# boxer_pH.net
KiCad netlist of a schematic drawn in Altium Designer
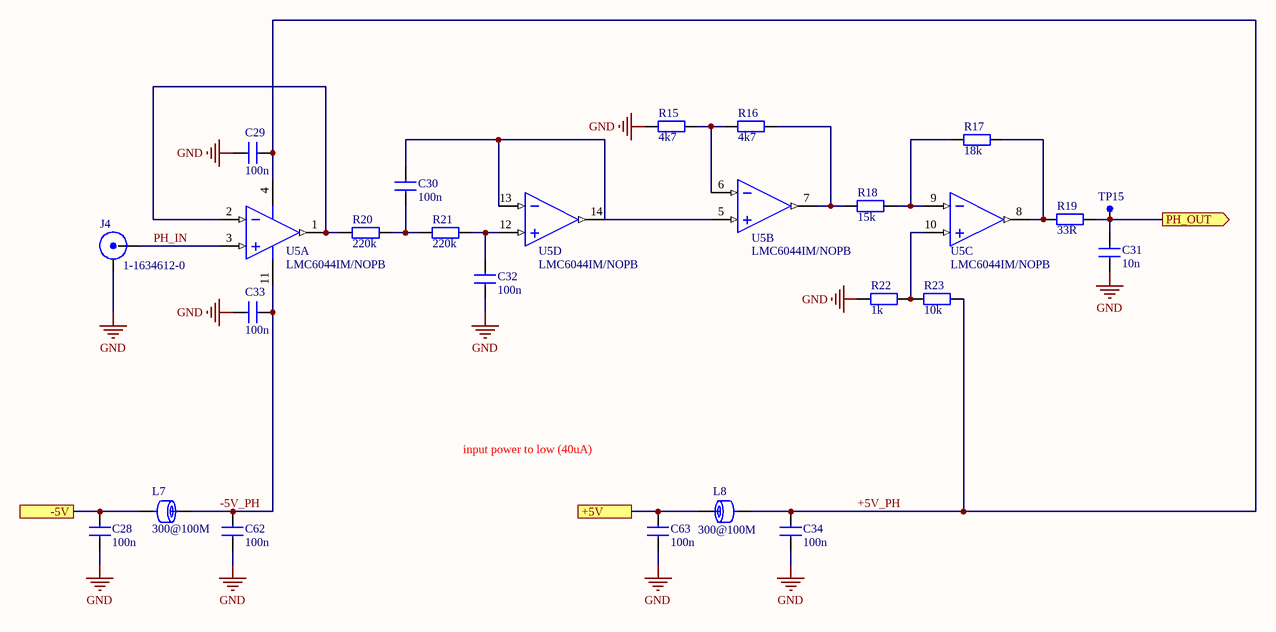
[diagram p0: boxer_pH.SchDoc]

(export (version "E")
  (design (tool "Eeschema 10.0.6"))
  (components
    (comp (ref "C28")
      (value "100n")
      (footprint "C_0805")
      (description "Capacitor")
      (libsource (lib "boxer_pas") (part "Capacitor"))
    )
    (comp (ref "C29")
      (value "100n")
      (footprint "C_0805")
      (description "Capacitor")
      (libsource (lib "boxer_pas") (part "Capacitor"))
    )
    (comp (ref "C30")
      (value "100n")
      (footprint "C_0805")
      (description "Capacitor")
      (libsource (lib "boxer_pas") (part "Capacitor"))
    )
    (comp (ref "C31")
      (value "10n")
      (footprint "C_0805")
      (description "Capacitor")
      (libsource (lib "boxer_pas") (part "Capacitor"))
    )
    (comp (ref "C32")
      (value "100n")
      (footprint "C_0805")
      (description "Capacitor")
      (libsource (lib "boxer_pas") (part "Capacitor"))
    )
    (comp (ref "C33")
      (value "100n")
      (footprint "C_0805")
      (description "Capacitor")
      (libsource (lib "boxer_pas") (part "Capacitor"))
    )
    (comp (ref "C34")
      (value "100n")
      (footprint "C_0805")
      (description "Capacitor")
      (libsource (lib "boxer_pas") (part "Capacitor"))
    )
    (comp (ref "C62")
      (value "100n")
      (footprint "C_0805")
      (description "Capacitor")
      (libsource (lib "boxer_pas") (part "Capacitor"))
    )
    (comp (ref "C63")
      (value "100n")
      (footprint "C_0805")
      (description "Capacitor")
      (libsource (lib "boxer_pas") (part "Capacitor"))
    )
    (comp (ref "J4")
      (value "1-1634612-0")
      (footprint "1-1634612-0")
      (description "BNC Elbow Connector")
      (libsource (lib "boxer_mechanical") (part "BNC"))
    )
    (comp (ref "L7")
      (value "300@100M")
      (footprint "L_0805")
      (description "Ferrite Bead")
      (fields (field (name "Comment") "742792031"))
      (libsource (lib "boxer_pas") (part "FB"))
    )
    (comp (ref "L8")
      (value "300@100M")
      (footprint "L_0805")
      (description "Ferrite Bead")
      (fields (field (name "Comment") "742792031"))
      (libsource (lib "") (part "FB_1"))
    )
    (comp (ref "R15")
      (value "4k7")
      (footprint "R_0805")
      (description "Resistor")
      (libsource (lib "boxer_pas") (part "Resistor"))
    )
    (comp (ref "R16")
      (value "4k7")
      (footprint "R_0805")
      (description "Resistor")
      (libsource (lib "boxer_pas") (part "Resistor"))
    )
    (comp (ref "R17")
      (value "18k")
      (footprint "R_0805")
      (description "Resistor")
      (libsource (lib "boxer_pas") (part "Resistor"))
    )
    (comp (ref "R18")
      (value "15k")
      (footprint "R_0805")
      (description "Resistor")
      (libsource (lib "boxer_pas") (part "Resistor"))
    )
    (comp (ref "R19")
      (value "33R")
      (footprint "R_0805")
      (description "Resistor")
      (libsource (lib "boxer_pas") (part "Resistor"))
    )
    (comp (ref "R20")
      (value "220k")
      (footprint "R_0805")
      (description "Resistor")
      (libsource (lib "boxer_pas") (part "Resistor"))
    )
    (comp (ref "R21")
      (value "220k")
      (footprint "R_0805")
      (description "Resistor")
      (libsource (lib "boxer_pas") (part "Resistor"))
    )
    (comp (ref "R22")
      (value "1k")
      (footprint "R_0805")
      (description "Resistor")
      (libsource (lib "boxer_pas") (part "Resistor"))
    )
    (comp (ref "R23")
      (value "10k")
      (footprint "R_1206")
      (description "Resistor")
      (libsource (lib "boxer_pas") (part "Resistor"))
    )
    (comp (ref "TP15")
      (value "TEST PAD")
      (footprint "PIN")
      (description "PAD 1.5mm")
      (libsource (lib "boxer_mechanical") (part "TEST_PAD"))
    )
    (comp (ref "U5")
      (value "LMC6044IM/NOPB")
      (footprint "SO14")
      (description "CMOS Quad Micropower Operational Amplifier, 14-pin Narrow SOIC")
      (libsource (lib "boxer_ic") (part "LMC6044IM/NOPB"))
    )
  )
  (nets
    (net (code "1") (name "/+5V") (class "Default")
      (node (ref "C63") (pin "2") (pinfunction "2_2") (pintype "passive"))
      (node (ref "L8") (pin "1") (pinfunction "1_1") (pintype "passive"))
    )
    (net (code "2") (name "/+5V_PH") (class "Default")
      (node (ref "C29") (pin "2") (pinfunction "2_2") (pintype "passive"))
      (node (ref "C34") (pin "2") (pinfunction "2_2") (pintype "passive"))
      (node (ref "L8") (pin "2") (pinfunction "2_2") (pintype "passive"))
      (node (ref "R23") (pin "2") (pinfunction "2_2") (pintype "passive"))
      (node (ref "U5") (pin "4") (pinfunction "VCC+_4") (pintype "power_in"))
    )
    (net (code "3") (name "/-5V") (class "Default")
      (node (ref "C28") (pin "2") (pinfunction "2_2") (pintype "passive"))
      (node (ref "L7") (pin "2") (pinfunction "2_2") (pintype "passive"))
    )
    (net (code "4") (name "/-5V_PH") (class "Default")
      (node (ref "C33") (pin "2") (pinfunction "2_2") (pintype "passive"))
      (node (ref "C62") (pin "2") (pinfunction "2_2") (pintype "passive"))
      (node (ref "L7") (pin "1") (pinfunction "1_1") (pintype "passive"))
      (node (ref "U5") (pin "11") (pinfunction "VCC-_11") (pintype "power_in"))
    )
    (net (code "5") (name "/PH_IN") (class "Default")
      (node (ref "J4") (pin "1") (pinfunction "OUT_1") (pintype "passive"))
      (node (ref "U5") (pin "3") (pinfunction "IN+_3") (pintype "input"))
    )
    (net (code "6") (name "/PH_OUT") (class "Default")
      (node (ref "C31") (pin "2") (pinfunction "2_2") (pintype "passive"))
      (node (ref "R19") (pin "2") (pinfunction "2_2") (pintype "passive"))
      (node (ref "TP15") (pin "1") (pinfunction "1_1") (pintype "passive"))
    )
    (net (code "7") (name "GND") (class "Default")
      (node (ref "C28") (pin "1") (pinfunction "1_1") (pintype "passive"))
      (node (ref "C29") (pin "1") (pinfunction "1_1") (pintype "passive"))
      (node (ref "C31") (pin "1") (pinfunction "1_1") (pintype "passive"))
      (node (ref "C32") (pin "1") (pinfunction "1_1") (pintype "passive"))
      (node (ref "C33") (pin "1") (pinfunction "1_1") (pintype "passive"))
      (node (ref "C34") (pin "1") (pinfunction "1_1") (pintype "passive"))
      (node (ref "C62") (pin "1") (pinfunction "1_1") (pintype "passive"))
      (node (ref "C63") (pin "1") (pinfunction "1_1") (pintype "passive"))
      (node (ref "J4") (pin "2") (pinfunction "GND_2") (pintype "passive"))
      (node (ref "R15") (pin "1") (pinfunction "1_1") (pintype "passive"))
      (node (ref "R22") (pin "1") (pinfunction "1_1") (pintype "passive"))
    )
    (net (code "8") (name "Net-(C30-Pad1)") (class "Default")
      (node (ref "C30") (pin "1") (pinfunction "1_1") (pintype "passive"))
      (node (ref "R20") (pin "2") (pinfunction "2_2") (pintype "passive"))
      (node (ref "R21") (pin "1") (pinfunction "1_1") (pintype "passive"))
    )
    (net (code "9") (name "Net-(U5A-IN-)") (class "Default")
      (node (ref "R20") (pin "1") (pinfunction "1_1") (pintype "passive"))
      (node (ref "U5") (pin "1") (pinfunction "OUT_1") (pintype "output"))
      (node (ref "U5") (pin "2") (pinfunction "IN-_2") (pintype "input"))
    )
    (net (code "10") (name "Net-(U5B-IN+)") (class "Default")
      (node (ref "C30") (pin "2") (pinfunction "2_2") (pintype "passive"))
      (node (ref "U5") (pin "13") (pinfunction "IN-_13") (pintype "input"))
      (node (ref "U5") (pin "14") (pinfunction "OUT_14") (pintype "output"))
      (node (ref "U5") (pin "5") (pinfunction "IN+_5") (pintype "input"))
    )
    (net (code "11") (name "Net-(U5B-IN-)") (class "Default")
      (node (ref "R15") (pin "2") (pinfunction "2_2") (pintype "passive"))
      (node (ref "R16") (pin "1") (pinfunction "1_1") (pintype "passive"))
      (node (ref "U5") (pin "6") (pinfunction "IN-_6") (pintype "input"))
    )
    (net (code "12") (name "Net-(U5B-OUT)") (class "Default")
      (node (ref "R16") (pin "2") (pinfunction "2_2") (pintype "passive"))
      (node (ref "R18") (pin "1") (pinfunction "1_1") (pintype "passive"))
      (node (ref "U5") (pin "7") (pinfunction "OUT_7") (pintype "output"))
    )
    (net (code "13") (name "Net-(U5C-IN+)") (class "Default")
      (node (ref "R22") (pin "2") (pinfunction "2_2") (pintype "passive"))
      (node (ref "R23") (pin "1") (pinfunction "1_1") (pintype "passive"))
      (node (ref "U5") (pin "10") (pinfunction "IN+_10") (pintype "input"))
    )
    (net (code "14") (name "Net-(U5C-IN-)") (class "Default")
      (node (ref "R17") (pin "1") (pinfunction "1_1") (pintype "passive"))
      (node (ref "R18") (pin "2") (pinfunction "2_2") (pintype "passive"))
      (node (ref "U5") (pin "9") (pinfunction "IN-_9") (pintype "input"))
    )
    (net (code "15") (name "Net-(U5C-OUT)") (class "Default")
      (node (ref "R17") (pin "2") (pinfunction "2_2") (pintype "passive"))
      (node (ref "R19") (pin "1") (pinfunction "1_1") (pintype "passive"))
      (node (ref "U5") (pin "8") (pinfunction "OUT_8") (pintype "output"))
    )
    (net (code "16") (name "Net-(U5D-IN+)") (class "Default")
      (node (ref "C32") (pin "2") (pinfunction "2_2") (pintype "passive"))
      (node (ref "R21") (pin "2") (pinfunction "2_2") (pintype "passive"))
      (node (ref "U5") (pin "12") (pinfunction "IN+_12") (pintype "input"))
    )
  )
)
